# stepper-v1.net
KiCad netlist of a schematic drawn in EAGLE
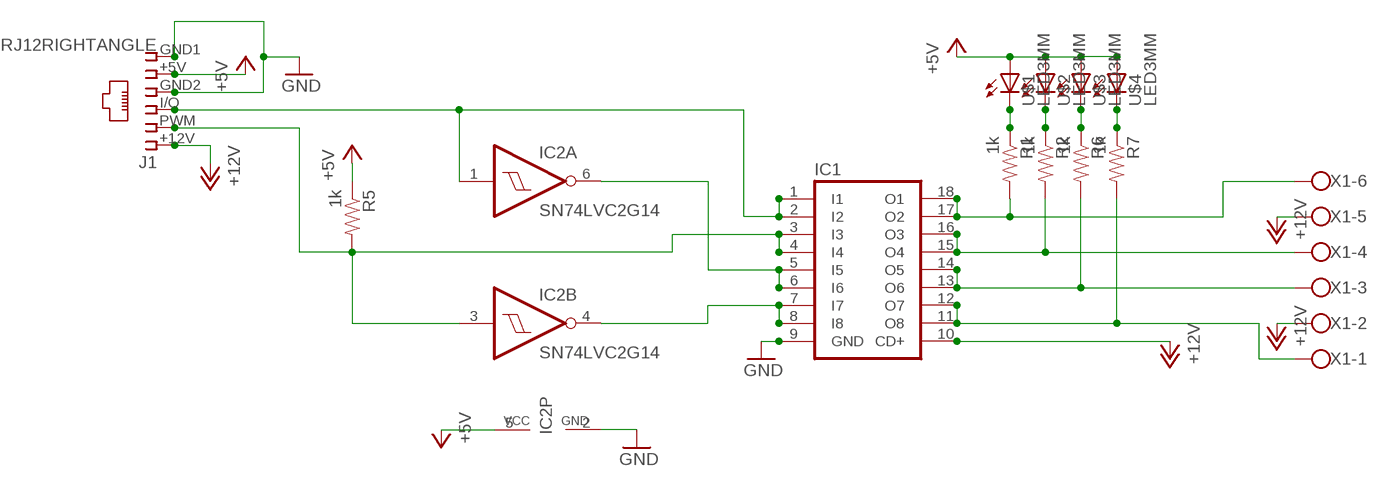
[diagram p0: schematic, sheet 1]

(export (version "E")
  (design (tool "Eeschema 10.0.6"))
  (components
    (comp (ref "IC1")
      (value "ULN2803A")
      (footprint "eagle-import:SO18W")
      (libsource (lib "eagle-import") (part "ULN2803A"))
    )
    (comp (ref "IC2")
      (value "SN74LVC2G14")
      (footprint "eagle-import:SOT23-6")
      (libsource (lib "eagle-import") (part "SN74LVC2G14"))
    )
    (comp (ref "J1")
      (value "RJ12RIGHTANGLE")
      (footprint "eagle-import:RJ12-RIGHTANGLE")
      (libsource (lib "eagle-import") (part "RJ12RIGHTANGLE"))
    )
    (comp (ref "R1")
      (value "1k")
      (footprint "eagle-import:1206")
      (libsource (lib "eagle-import") (part "RESISTOR1206"))
    )
    (comp (ref "R2")
      (value "1k")
      (footprint "eagle-import:1206")
      (libsource (lib "eagle-import") (part "RESISTOR1206"))
    )
    (comp (ref "R5")
      (value "1k")
      (footprint "eagle-import:1206")
      (libsource (lib "eagle-import") (part "RESISTOR1206"))
    )
    (comp (ref "R6")
      (value "1k")
      (footprint "eagle-import:1206")
      (libsource (lib "eagle-import") (part "RESISTOR1206"))
    )
    (comp (ref "R7")
      (value "1k")
      (footprint "eagle-import:1206")
      (libsource (lib "eagle-import") (part "RESISTOR1206"))
    )
    (comp (ref "U$1")
      (value "LED3MM")
      (footprint "eagle-import:LED3MM")
      (libsource (lib "eagle-import") (part "LED3MM"))
    )
    (comp (ref "U$2")
      (value "LED3MM")
      (footprint "eagle-import:LED3MM")
      (libsource (lib "eagle-import") (part "LED3MM"))
    )
    (comp (ref "U$3")
      (value "LED3MM")
      (footprint "eagle-import:LED3MM")
      (libsource (lib "eagle-import") (part "LED3MM"))
    )
    (comp (ref "U$4")
      (value "LED3MM")
      (footprint "eagle-import:LED3MM")
      (libsource (lib "eagle-import") (part "LED3MM"))
    )
    (comp (ref "X1")
      (value "W237-6")
      (footprint "eagle-import:W237-6")
      (libsource (lib "eagle-import") (part "W237-6"))
    )
  )
  (nets
    (net (code "1") (name "+5V") (class "Default")
      (node (ref "IC2") (pin "5") (pinfunction "VCC_5") (pintype "power_in"))
      (node (ref "J1") (pin "+5V") (pinfunction "5_+5V") (pintype "power_in"))
      (node (ref "R5") (pin "1") (pinfunction "1_1") (pintype "passive"))
      (node (ref "U$1") (pin "A") (pinfunction "A_A") (pintype "passive"))
      (node (ref "U$2") (pin "A") (pinfunction "A_A") (pintype "passive"))
      (node (ref "U$3") (pin "A") (pinfunction "A_A") (pintype "passive"))
      (node (ref "U$4") (pin "A") (pinfunction "A_A") (pintype "passive"))
    )
    (net (code "2") (name "+12V") (class "Default")
      (node (ref "IC1") (pin "10") (pinfunction "CD+_10") (pintype "passive"))
      (node (ref "J1") (pin "+12V") (pinfunction "1_+12V") (pintype "power_in"))
      (node (ref "X1") (pin "2") (pinfunction "KL_2") (pintype "passive"))
      (node (ref "X1") (pin "5") (pinfunction "KL_5") (pintype "passive"))
    )
    (net (code "3") (name "GND") (class "Default")
      (node (ref "IC1") (pin "9") (pinfunction "GND_9") (pintype "power_in"))
      (node (ref "IC2") (pin "2") (pinfunction "GND_2") (pintype "power_in"))
      (node (ref "J1") (pin "GND1") (pinfunction "6_GND1") (pintype "power_in"))
      (node (ref "J1") (pin "GND2") (pinfunction "4_GND2") (pintype "power_in"))
    )
    (net (code "4") (name "Net-(IC1-I1)") (class "Default")
      (node (ref "IC1") (pin "1") (pinfunction "I1_1") (pintype "input"))
      (node (ref "IC1") (pin "2") (pinfunction "I2_2") (pintype "input"))
      (node (ref "IC2") (pin "1") (pinfunction "I_1") (pintype "input"))
      (node (ref "J1") (pin "I/O") (pinfunction "3_I/O") (pintype "bidirectional"))
    )
    (net (code "5") (name "Net-(IC1-I3)") (class "Default")
      (node (ref "IC1") (pin "3") (pinfunction "I3_3") (pintype "input"))
      (node (ref "IC1") (pin "4") (pinfunction "I4_4") (pintype "input"))
      (node (ref "IC2") (pin "3") (pinfunction "I_3") (pintype "input"))
      (node (ref "J1") (pin "PWM") (pinfunction "2_PWM") (pintype "bidirectional"))
      (node (ref "R5") (pin "2") (pinfunction "2_2") (pintype "passive"))
    )
    (net (code "6") (name "Net-(IC1-I5)") (class "Default")
      (node (ref "IC1") (pin "5") (pinfunction "I5_5") (pintype "input"))
      (node (ref "IC1") (pin "6") (pinfunction "I6_6") (pintype "input"))
      (node (ref "IC2") (pin "6") (pinfunction "O_6") (pintype "output"))
    )
    (net (code "7") (name "Net-(IC1-I7)") (class "Default")
      (node (ref "IC1") (pin "7") (pinfunction "I7_7") (pintype "input"))
      (node (ref "IC1") (pin "8") (pinfunction "I8_8") (pintype "input"))
      (node (ref "IC2") (pin "4") (pinfunction "O_4") (pintype "output"))
    )
    (net (code "8") (name "Net-(IC1-O1)") (class "Default")
      (node (ref "IC1") (pin "17") (pinfunction "O2_17") (pintype "open_collector"))
      (node (ref "IC1") (pin "18") (pinfunction "O1_18") (pintype "open_collector"))
      (node (ref "R1") (pin "2") (pinfunction "2_2") (pintype "passive"))
      (node (ref "X1") (pin "6") (pinfunction "KL_6") (pintype "passive"))
    )
    (net (code "9") (name "Net-(IC1-O3)") (class "Default")
      (node (ref "IC1") (pin "15") (pinfunction "O4_15") (pintype "open_collector"))
      (node (ref "IC1") (pin "16") (pinfunction "O3_16") (pintype "open_collector"))
      (node (ref "R2") (pin "2") (pinfunction "2_2") (pintype "passive"))
      (node (ref "X1") (pin "4") (pinfunction "KL_4") (pintype "passive"))
    )
    (net (code "10") (name "Net-(IC1-O5)") (class "Default")
      (node (ref "IC1") (pin "13") (pinfunction "O6_13") (pintype "open_collector"))
      (node (ref "IC1") (pin "14") (pinfunction "O5_14") (pintype "open_collector"))
      (node (ref "R6") (pin "2") (pinfunction "2_2") (pintype "passive"))
      (node (ref "X1") (pin "3") (pinfunction "KL_3") (pintype "passive"))
    )
    (net (code "11") (name "Net-(IC1-O7)") (class "Default")
      (node (ref "IC1") (pin "11") (pinfunction "O8_11") (pintype "open_collector"))
      (node (ref "IC1") (pin "12") (pinfunction "O7_12") (pintype "open_collector"))
      (node (ref "R7") (pin "2") (pinfunction "2_2") (pintype "passive"))
      (node (ref "X1") (pin "1") (pinfunction "KL_1") (pintype "passive"))
    )
    (net (code "12") (name "Net-(U$1-C)") (class "Default")
      (node (ref "R1") (pin "1") (pinfunction "1_1") (pintype "passive"))
      (node (ref "U$1") (pin "K") (pinfunction "C_K") (pintype "passive"))
    )
    (net (code "13") (name "Net-(U$2-C)") (class "Default")
      (node (ref "R2") (pin "1") (pinfunction "1_1") (pintype "passive"))
      (node (ref "U$2") (pin "K") (pinfunction "C_K") (pintype "passive"))
    )
    (net (code "14") (name "Net-(U$3-C)") (class "Default")
      (node (ref "R6") (pin "1") (pinfunction "1_1") (pintype "passive"))
      (node (ref "U$3") (pin "K") (pinfunction "C_K") (pintype "passive"))
    )
    (net (code "15") (name "Net-(U$4-C)") (class "Default")
      (node (ref "R7") (pin "1") (pinfunction "1_1") (pintype "passive"))
      (node (ref "U$4") (pin "K") (pinfunction "C_K") (pintype "passive"))
    )
  )
)
